# RobotCtrl_V2_Mother-board.net
KiCad netlist of a schematic drawn in Altium Designer
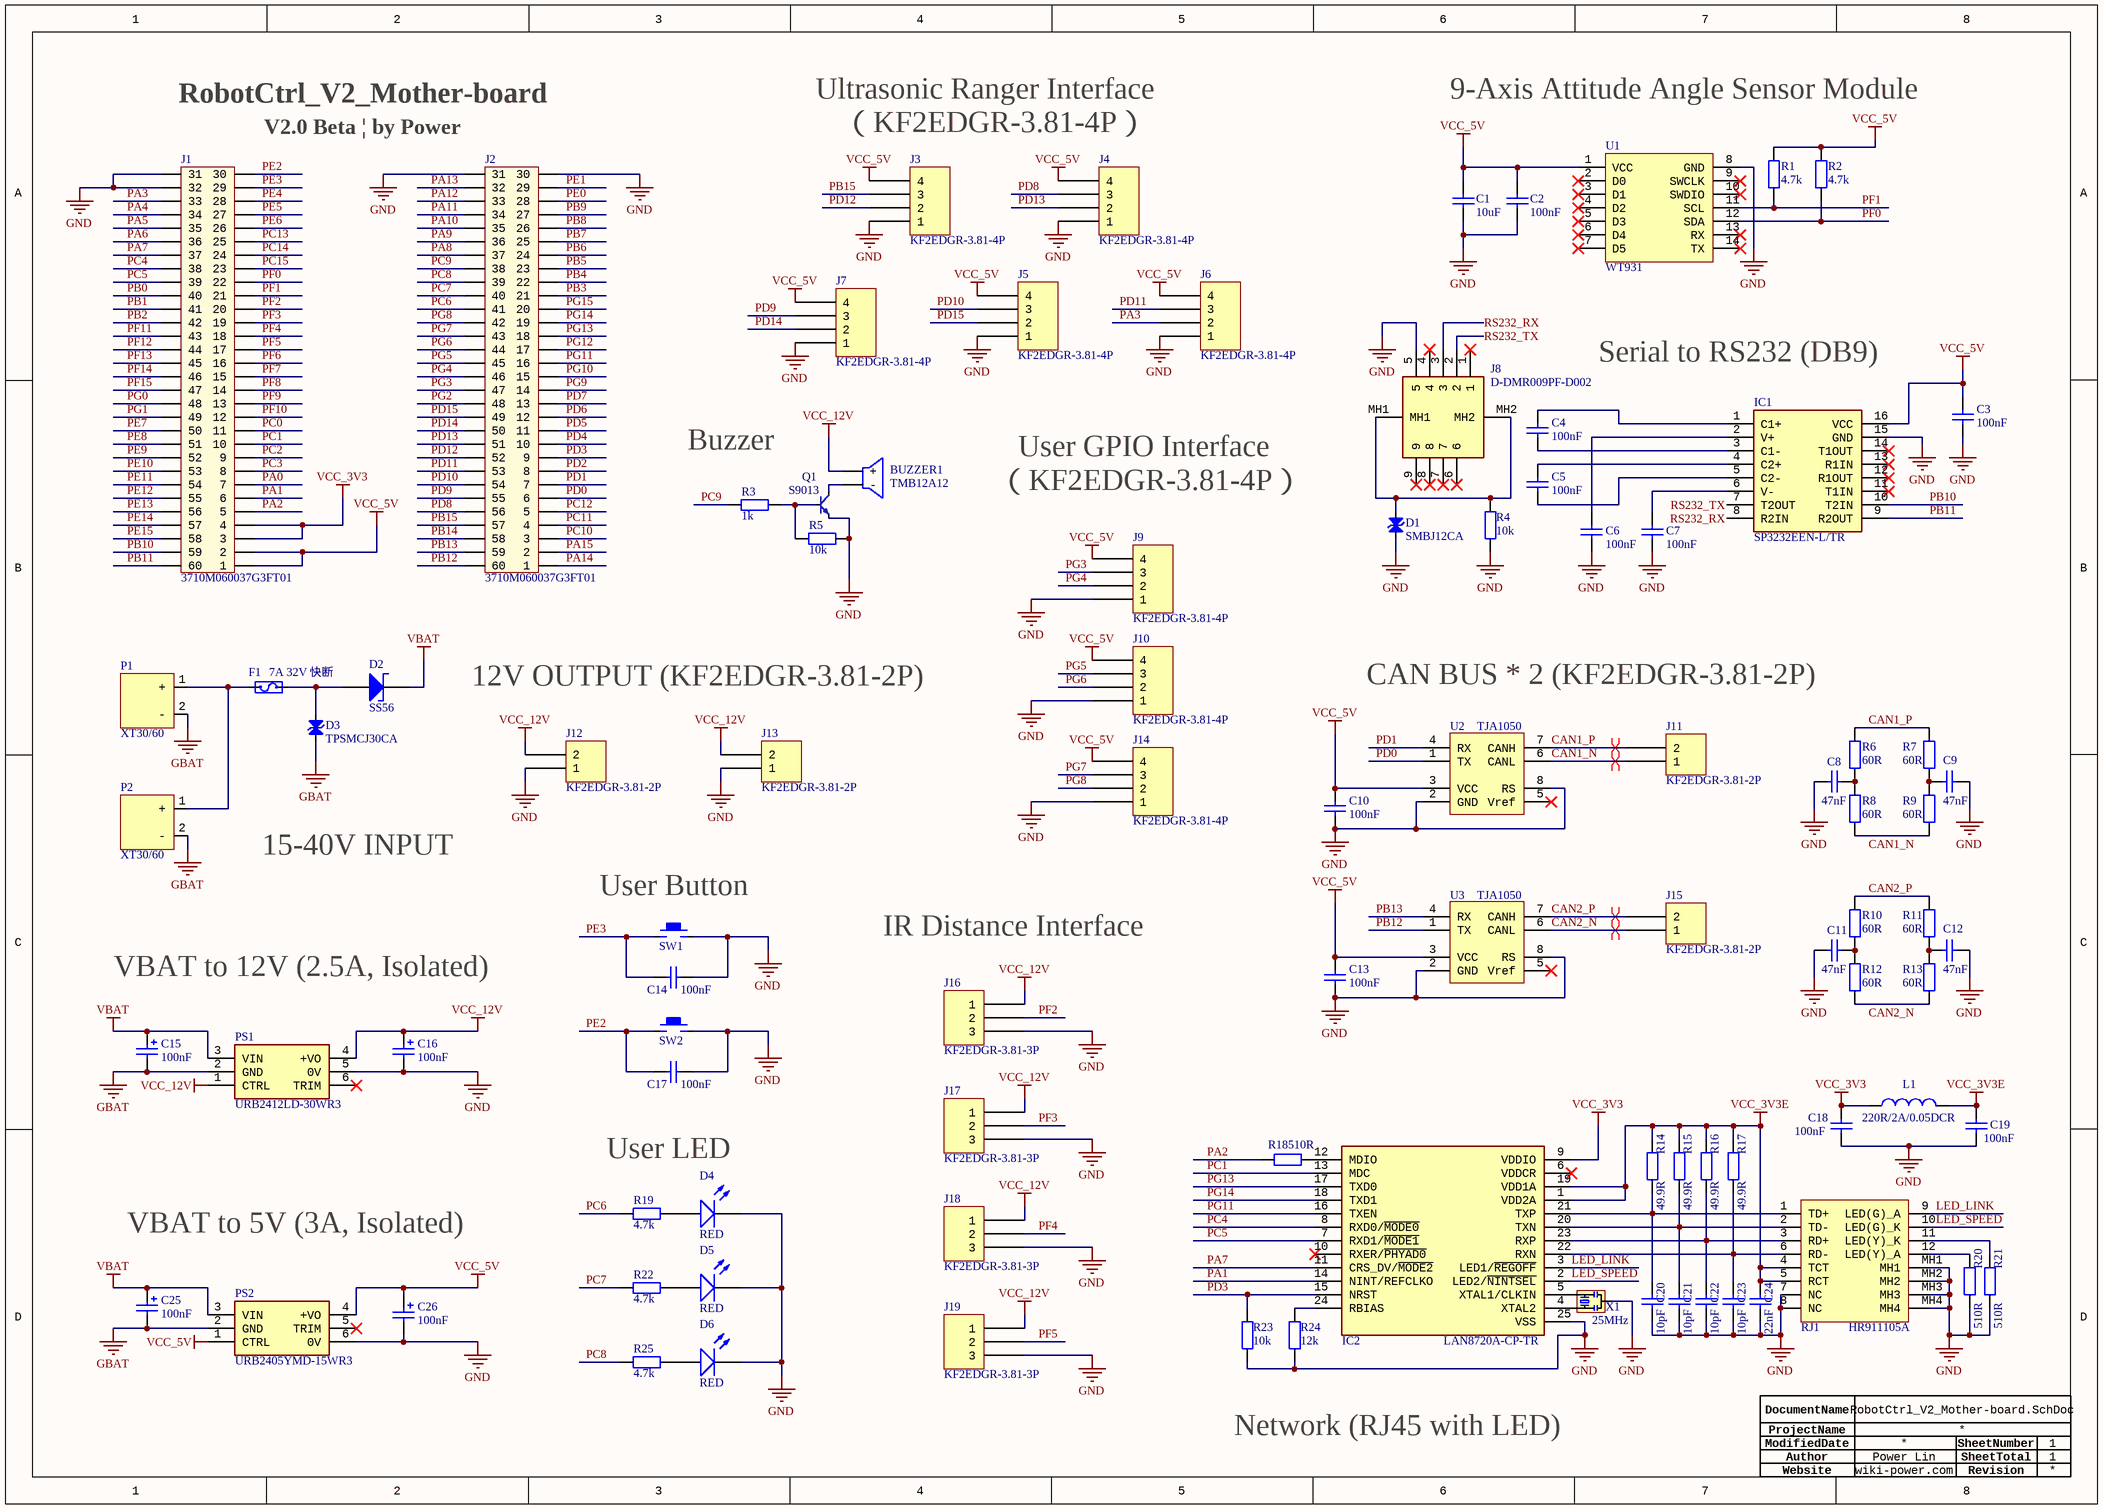
[diagram p0: RobotCtrl_V2_Mother-board.SchDoc]

(export (version "E")
  (design (tool "Eeschema 10.0.6"))
  (components
    (comp (ref "BUZZER1")
      (value "TMB12A12")
      (footprint "DIP,P=7.6mm")
      (description "TMB12A12 有源蜂鸣器")
      (libsource (lib "Power_Lib_Altium") (part "BUZZER"))
    )
    (comp (ref "C1")
      (value "10uF")
      (footprint "CAP-0603")
      (description "贴片电容")
      (libsource (lib "Power_Lib_Altium") (part "CAP"))
    )
    (comp (ref "C2")
      (value "100nF")
      (footprint "CAP-0603")
      (description "贴片电容")
      (libsource (lib "Power_Lib_Altium") (part "CAP"))
    )
    (comp (ref "C3")
      (value "100nF")
      (footprint "CAP-0603")
      (description "贴片电容")
      (libsource (lib "Power_Lib_Altium") (part "CAP"))
    )
    (comp (ref "C4")
      (value "100nF")
      (footprint "CAP-0603")
      (description "贴片电容")
      (libsource (lib "Power_Lib_Altium") (part "CAP"))
    )
    (comp (ref "C5")
      (value "100nF")
      (footprint "CAP-0603")
      (description "贴片电容")
      (libsource (lib "Power_Lib_Altium") (part "CAP"))
    )
    (comp (ref "C6")
      (value "100nF")
      (footprint "CAP-0603")
      (description "贴片电容")
      (libsource (lib "Power_Lib_Altium") (part "CAP"))
    )
    (comp (ref "C7")
      (value "100nF")
      (footprint "CAP-0603")
      (description "贴片电容")
      (libsource (lib "Power_Lib_Altium") (part "CAP"))
    )
    (comp (ref "C8")
      (value "47nF")
      (footprint "CAP-0603")
      (description "贴片电容")
      (libsource (lib "Power_Lib_Altium") (part "CAP"))
    )
    (comp (ref "C9")
      (value "47nF")
      (footprint "CAP-0603")
      (description "贴片电容")
      (libsource (lib "Power_Lib_Altium") (part "CAP"))
    )
    (comp (ref "C10")
      (value "100nF")
      (footprint "CAP-0603")
      (description "贴片电容")
      (libsource (lib "Power_Lib_Altium") (part "CAP"))
    )
    (comp (ref "C11")
      (value "47nF")
      (footprint "CAP-0603")
      (description "贴片电容")
      (libsource (lib "Power_Lib_Altium") (part "CAP"))
    )
    (comp (ref "C12")
      (value "47nF")
      (footprint "CAP-0603")
      (description "贴片电容")
      (libsource (lib "Power_Lib_Altium") (part "CAP"))
    )
    (comp (ref "C13")
      (value "100nF")
      (footprint "CAP-0603")
      (description "贴片电容")
      (libsource (lib "Power_Lib_Altium") (part "CAP"))
    )
    (comp (ref "C14")
      (value "100nF")
      (footprint "CAP-0603")
      (description "贴片电容")
      (libsource (lib "Power_Lib_Altium") (part "CAP"))
    )
    (comp (ref "C15")
      (value "100nF")
      (footprint "CAP-AUX-3216")
      (description "KM101M050F115A")
      (libsource (lib "Power_Lib_Altium") (part "CAP-POL"))
    )
    (comp (ref "C16")
      (value "100nF")
      (footprint "CAP-AUX-3216")
      (description "KM101M050F115A")
      (libsource (lib "Power_Lib_Altium") (part "CAP-POL"))
    )
    (comp (ref "C17")
      (value "100nF")
      (footprint "CAP-0603")
      (description "贴片电容")
      (libsource (lib "Power_Lib_Altium") (part "CAP"))
    )
    (comp (ref "C18")
      (value "100nF")
      (footprint "CAP-0603")
      (description "贴片电容")
      (libsource (lib "Power_Lib_Altium") (part "CAP"))
    )
    (comp (ref "C19")
      (value "100nF")
      (footprint "CAP-0603")
      (description "贴片电容")
      (libsource (lib "Power_Lib_Altium") (part "CAP"))
    )
    (comp (ref "C20")
      (value "10pF")
      (footprint "CAP-0603")
      (description "贴片电容")
      (libsource (lib "Power_Lib_Altium") (part "CAP"))
    )
    (comp (ref "C21")
      (value "10pF")
      (footprint "CAP-0603")
      (description "贴片电容")
      (libsource (lib "Power_Lib_Altium") (part "CAP"))
    )
    (comp (ref "C22")
      (value "10pF")
      (footprint "CAP-0603")
      (description "贴片电容")
      (libsource (lib "Power_Lib_Altium") (part "CAP"))
    )
    (comp (ref "C23")
      (value "10pF")
      (footprint "CAP-0603")
      (description "贴片电容")
      (libsource (lib "Power_Lib_Altium") (part "CAP"))
    )
    (comp (ref "C24")
      (value "22nF")
      (footprint "CAP-0603")
      (description "贴片电容")
      (libsource (lib "Power_Lib_Altium") (part "CAP"))
    )
    (comp (ref "C25")
      (value "100nF")
      (footprint "CAP-AUX-3216")
      (description "KM101M050F115A")
      (libsource (lib "Power_Lib_Altium") (part "CAP-POL"))
    )
    (comp (ref "C26")
      (value "100nF")
      (footprint "CAP-AUX-3216")
      (description "KM101M050F115A")
      (libsource (lib "Power_Lib_Altium") (part "CAP-POL"))
    )
    (comp (ref "D1")
      (value "SMBJ12CA")
      (footprint "DO-214AA/SMB")
      (libsource (lib "Power_Lib_Altium") (part "TVS_C"))
    )
    (comp (ref "D2")
      (value "SS56")
      (footprint "DO-214AB/SMC")
      (description "肖特基二极管")
      (libsource (lib "Power_Lib_Altium") (part "DIODE_Schottky"))
    )
    (comp (ref "D3")
      (value "TPSMCJ30CA")
      (footprint "DO-214AB/SMC")
      (libsource (lib "Power_Lib_Altium") (part "TVS_C"))
    )
    (comp (ref "D4")
      (value "RED")
      (footprint "LED-0603")
      (description "发光二极管")
      (libsource (lib "Power_Lib_Altium") (part "LED"))
    )
    (comp (ref "D5")
      (value "RED")
      (footprint "LED-0603")
      (description "发光二极管")
      (libsource (lib "Power_Lib_Altium") (part "LED"))
    )
    (comp (ref "D6")
      (value "RED")
      (footprint "LED-0603")
      (description "发光二极管")
      (libsource (lib "Power_Lib_Altium") (part "LED"))
    )
    (comp (ref "F1")
      (value "7A 32V 快断")
      (footprint "FUSE_1206")
      (description "0437007.WR")
      (libsource (lib "Power_Lib_Altium") (part "Fuse"))
    )
    (comp (ref "IC1")
      (value "SP3232EEN-L/TR")
      (footprint "SOIC-16_150mil")
      (description "RS232 芯片")
      (fields (field (name "MOUSER PART NUMBER") "701-SP3232EEN-L/TR"))
      (libsource (lib "Power_Lib_Altium") (part "SP3232EEN"))
    )
    (comp (ref "IC2")
      (value "LAN8720A-CP-TR")
      (footprint "QFN-24-4x4")
      (description "Integrated Circuit")
      (fields (field (name "MOUSER PART NUMBER") "886-LAN8720A-CP-TR"))
      (libsource (lib "Power_Lib_Altium") (part "LAN8720A-CP-TR"))
    )
    (comp (ref "J1")
      (value "3710M060037G3FT01")
      (footprint "3710M060037G3FT01")
      (description "B2B Connector")
      (libsource (lib "Power_Lib_Altium") (part "3710M/F"))
    )
    (comp (ref "J2")
      (value "3710M060037G3FT01")
      (footprint "3710M060037G3FT01")
      (description "B2B Connector")
      (libsource (lib "Power_Lib_Altium") (part "3710M/F"))
    )
    (comp (ref "J3")
      (value "KF2EDGR-3.81-4P")
      (footprint "FCI 06-381-4PIN")
      (description "TERM BLOCK HDR 4POS 90DEG 3.81MM")
      (fields (field (name "PART NUMBER") "OQ0432510000G") (field (name "MANUFACTURER") "Amphenol Anytek"))
      (libsource (lib "Power_Lib_Altium") (part "KF2EDGR-3.81-4P"))
    )
    (comp (ref "J4")
      (value "KF2EDGR-3.81-4P")
      (footprint "FCI 06-381-4PIN")
      (description "TERM BLOCK HDR 4POS 90DEG 3.81MM")
      (fields (field (name "PART NUMBER") "OQ0432510000G") (field (name "MANUFACTURER") "Amphenol Anytek"))
      (libsource (lib "Power_Lib_Altium") (part "KF2EDGR-3.81-4P"))
    )
    (comp (ref "J5")
      (value "KF2EDGR-3.81-4P")
      (footprint "FCI 06-381-4PIN")
      (description "TERM BLOCK HDR 4POS 90DEG 3.81MM")
      (fields (field (name "PART NUMBER") "OQ0432510000G") (field (name "MANUFACTURER") "Amphenol Anytek"))
      (libsource (lib "Power_Lib_Altium") (part "KF2EDGR-3.81-4P"))
    )
    (comp (ref "J6")
      (value "KF2EDGR-3.81-4P")
      (footprint "FCI 06-381-4PIN")
      (description "TERM BLOCK HDR 4POS 90DEG 3.81MM")
      (fields (field (name "PART NUMBER") "OQ0432510000G") (field (name "MANUFACTURER") "Amphenol Anytek"))
      (libsource (lib "Power_Lib_Altium") (part "KF2EDGR-3.81-4P"))
    )
    (comp (ref "J7")
      (value "KF2EDGR-3.81-4P")
      (footprint "FCI 06-381-4PIN")
      (description "TERM BLOCK HDR 4POS 90DEG 3.81MM")
      (fields (field (name "PART NUMBER") "OQ0432510000G") (field (name "MANUFACTURER") "Amphenol Anytek"))
      (libsource (lib "Power_Lib_Altium") (part "KF2EDGR-3.81-4P"))
    )
    (comp (ref "J8")
      (value "D-DMR009PF-D002")
      (footprint "Through Hole,P=2.77mm")
      (description "D-Sub 连接器")
      (fields
        (field (name "MANUFACTURER_PART_NUMBER") "5747844-5")
        (field (name "MOUSER PART NUMBER") "571-5747844-5")
      )
      (libsource (lib "Power_Lib_Altium") (part "DB9"))
    )
    (comp (ref "J9")
      (value "KF2EDGR-3.81-4P")
      (footprint "FCI 06-381-4PIN")
      (description "TERM BLOCK HDR 4POS 90DEG 3.81MM")
      (fields (field (name "PART NUMBER") "OQ0432510000G") (field (name "MANUFACTURER") "Amphenol Anytek"))
      (libsource (lib "Power_Lib_Altium") (part "KF2EDGR-3.81-4P"))
    )
    (comp (ref "J10")
      (value "KF2EDGR-3.81-4P")
      (footprint "FCI 06-381-4PIN")
      (description "TERM BLOCK HDR 4POS 90DEG 3.81MM")
      (fields (field (name "PART NUMBER") "OQ0432510000G") (field (name "MANUFACTURER") "Amphenol Anytek"))
      (libsource (lib "Power_Lib_Altium") (part "KF2EDGR-3.81-4P"))
    )
    (comp (ref "J11")
      (value "KF2EDGR-3.81-2P")
      (footprint "FCI 06-381-2PIN")
      (description "TERM BLOCK HDR 2POS 90DEG 3.81MM")
      (fields (field (name "PART NUMBER") "OQ0232510000G") (field (name "MANUFACTURER") "Amphenol Anytek"))
      (libsource (lib "Power_Lib_Altium") (part "KF2EDGR-3.81-2P"))
    )
    (comp (ref "J12")
      (value "KF2EDGR-3.81-2P")
      (footprint "FCI 06-381-2PIN")
      (description "TERM BLOCK HDR 2POS 90DEG 3.81MM")
      (fields (field (name "PART NUMBER") "OQ0232510000G") (field (name "MANUFACTURER") "Amphenol Anytek"))
      (libsource (lib "Power_Lib_Altium") (part "KF2EDGR-3.81-2P"))
    )
    (comp (ref "J13")
      (value "KF2EDGR-3.81-2P")
      (footprint "FCI 06-381-2PIN")
      (description "TERM BLOCK HDR 2POS 90DEG 3.81MM")
      (fields (field (name "PART NUMBER") "OQ0232510000G") (field (name "MANUFACTURER") "Amphenol Anytek"))
      (libsource (lib "Power_Lib_Altium") (part "KF2EDGR-3.81-2P"))
    )
    (comp (ref "J14")
      (value "KF2EDGR-3.81-4P")
      (footprint "FCI 06-381-4PIN")
      (description "TERM BLOCK HDR 4POS 90DEG 3.81MM")
      (fields (field (name "PART NUMBER") "OQ0432510000G") (field (name "MANUFACTURER") "Amphenol Anytek"))
      (libsource (lib "Power_Lib_Altium") (part "KF2EDGR-3.81-4P"))
    )
    (comp (ref "J15")
      (value "KF2EDGR-3.81-2P")
      (footprint "FCI 06-381-2PIN")
      (description "TERM BLOCK HDR 2POS 90DEG 3.81MM")
      (fields (field (name "PART NUMBER") "OQ0232510000G") (field (name "MANUFACTURER") "Amphenol Anytek"))
      (libsource (lib "Power_Lib_Altium") (part "KF2EDGR-3.81-2P"))
    )
    (comp (ref "J16")
      (value "KF2EDGR-3.81-3P")
      (footprint "FCI 06-381-3PIN")
      (description "TERM BLOCK HDR 3POS 90DEG 3.81MM")
      (fields (field (name "MANUFACTURER") "Amphenol Anytek") (field (name "PART NUMBER") "OQ0332510000G"))
      (libsource (lib "Power_Lib_Altium") (part "KF2EDGR-3.81-3P"))
    )
    (comp (ref "J17")
      (value "KF2EDGR-3.81-3P")
      (footprint "FCI 06-381-3PIN")
      (description "TERM BLOCK HDR 3POS 90DEG 3.81MM")
      (fields (field (name "MANUFACTURER") "Amphenol Anytek") (field (name "PART NUMBER") "OQ0332510000G"))
      (libsource (lib "Power_Lib_Altium") (part "KF2EDGR-3.81-3P"))
    )
    (comp (ref "J18")
      (value "KF2EDGR-3.81-3P")
      (footprint "FCI 06-381-3PIN")
      (description "TERM BLOCK HDR 3POS 90DEG 3.81MM")
      (fields (field (name "MANUFACTURER") "Amphenol Anytek") (field (name "PART NUMBER") "OQ0332510000G"))
      (libsource (lib "Power_Lib_Altium") (part "KF2EDGR-3.81-3P"))
    )
    (comp (ref "J19")
      (value "KF2EDGR-3.81-3P")
      (footprint "FCI 06-381-3PIN")
      (description "TERM BLOCK HDR 3POS 90DEG 3.81MM")
      (fields (field (name "MANUFACTURER") "Amphenol Anytek") (field (name "PART NUMBER") "OQ0332510000G"))
      (libsource (lib "Power_Lib_Altium") (part "KF2EDGR-3.81-3P"))
    )
    (comp (ref "L1")
      (value "220R/2A/0.05DCR")
      (footprint "L-0603")
      (description "BLM18KG221SN1D")
      (libsource (lib "Power_Lib_Altium") (part "BEAD"))
    )
    (comp (ref "P1")
      (value "XT30/60")
      (footprint "XT60PW-M")
      (libsource (lib "Power_Lib_Altium") (part "XT30/60"))
    )
    (comp (ref "P2")
      (value "XT30/60")
      (footprint "XT60PW-M")
      (libsource (lib "Power_Lib_Altium") (part "XT30/60"))
    )
    (comp (ref "PS1")
      (value "URB2412LD-30WR3")
      (footprint "URB2412LD30WR3")
      (description "金升阳隔离电源")
      (fields (field (name "MANUFACTURER_PART_NUMBER") "URB2412LD-30WHR3"))
      (libsource (lib "Power_Lib_Altium") (part "URB2412LD-30WR3"))
    )
    (comp (ref "PS2")
      (value "URB2405YMD-15WR3")
      (footprint "URB2405YMD15WR3")
      (description "金升阳隔离电源")
      (fields (field (name "MANUFACTURER_PART_NUMBER") "URB2405YMD-10WR3"))
      (libsource (lib "Power_Lib_Altium") (part "URB2405YMD-15WR3"))
    )
    (comp (ref "Q1")
      (value "S9013")
      (footprint "SOT-23-3")
      (libsource (lib "Power_Lib_Altium") (part "BJT_NPN"))
    )
    (comp (ref "R1")
      (value "4.7k")
      (footprint "R-0603")
      (description "贴片电阻")
      (libsource (lib "") (part "RES_1"))
    )
    (comp (ref "R2")
      (value "4.7k")
      (footprint "R-0603")
      (description "贴片电阻")
      (libsource (lib "") (part "RES_1"))
    )
    (comp (ref "R3")
      (value "1k")
      (footprint "R-0603")
      (description "贴片电阻")
      (libsource (lib "") (part "RES_3"))
    )
    (comp (ref "R4")
      (value "10k")
      (footprint "R-0603")
      (description "贴片电阻")
      (libsource (lib "") (part "RES_1"))
    )
    (comp (ref "R5")
      (value "10k")
      (footprint "R-0603")
      (description "贴片电阻")
      (libsource (lib "Power_Lib_Altium") (part "RES"))
    )
    (comp (ref "R6")
      (value "60R")
      (footprint "R-0603")
      (description "贴片电阻")
      (libsource (lib "") (part "RES_2"))
    )
    (comp (ref "R7")
      (value "60R")
      (footprint "R-0603")
      (description "贴片电阻")
      (libsource (lib "") (part "RES_1"))
    )
    (comp (ref "R8")
      (value "60R")
      (footprint "R-0603")
      (description "贴片电阻")
      (libsource (lib "") (part "RES_2"))
    )
    (comp (ref "R9")
      (value "60R")
      (footprint "R-0603")
      (description "贴片电阻")
      (libsource (lib "") (part "RES_1"))
    )
    (comp (ref "R10")
      (value "60R")
      (footprint "R-0603")
      (description "贴片电阻")
      (libsource (lib "") (part "RES_2"))
    )
    (comp (ref "R11")
      (value "60R")
      (footprint "R-0603")
      (description "贴片电阻")
      (libsource (lib "") (part "RES_1"))
    )
    (comp (ref "R12")
      (value "60R")
      (footprint "R-0603")
      (description "贴片电阻")
      (libsource (lib "") (part "RES_2"))
    )
    (comp (ref "R13")
      (value "60R")
      (footprint "R-0603")
      (description "贴片电阻")
      (libsource (lib "") (part "RES_1"))
    )
    (comp (ref "R14")
      (value "49.9R")
      (footprint "R-0603")
      (description "贴片电阻")
      (libsource (lib "") (part "RES_1"))
    )
    (comp (ref "R15")
      (value "49.9R")
      (footprint "R-0603")
      (description "贴片电阻")
      (libsource (lib "") (part "RES_1"))
    )
    (comp (ref "R16")
      (value "49.9R")
      (footprint "R-0603")
      (description "贴片电阻")
      (libsource (lib "") (part "RES_1"))
    )
    (comp (ref "R17")
      (value "49.9R")
      (footprint "R-0603")
      (description "贴片电阻")
      (libsource (lib "") (part "RES_1"))
    )
    (comp (ref "R18")
      (value "510R")
      (footprint "R-0603")
      (description "贴片电阻")
      (libsource (lib "Power_Lib_Altium") (part "RES"))
    )
    (comp (ref "R19")
      (value "4.7k")
      (footprint "R-0603")
      (description "贴片电阻")
      (libsource (lib "Power_Lib_Altium") (part "RES"))
    )
    (comp (ref "R20")
      (value "510R")
      (footprint "R-0603")
      (description "贴片电阻")
      (libsource (lib "") (part "RES_1"))
    )
    (comp (ref "R21")
      (value "510R")
      (footprint "R-0603")
      (description "贴片电阻")
      (libsource (lib "") (part "RES_1"))
    )
    (comp (ref "R22")
      (value "4.7k")
      (footprint "R-0603")
      (description "贴片电阻")
      (libsource (lib "Power_Lib_Altium") (part "RES"))
    )
    (comp (ref "R23")
      (value "10k")
      (footprint "R-0603")
      (description "贴片电阻")
      (libsource (lib "") (part "RES_2"))
    )
    (comp (ref "R24")
      (value "12k")
      (footprint "R-0603")
      (description "贴片电阻")
      (libsource (lib "") (part "RES_2"))
    )
    (comp (ref "R25")
      (value "4.7k")
      (footprint "R-0603")
      (description "贴片电阻")
      (libsource (lib "Power_Lib_Altium") (part "RES"))
    )
    (comp (ref "RJ1")
      (value "HR911105A")
      (footprint "HR911105A")
      (libsource (lib "Power_Lib_Altium") (part "RJ45_LED"))
    )
    (comp (ref "SW1")
      (value "KEY")
      (footprint "KEY-4P-4.2*3.4*2.5")
      (description "按键开关")
      (libsource (lib "Power_Lib_Altium") (part "KEY"))
    )
    (comp (ref "SW2")
      (value "KEY")
      (footprint "KEY-4P-4.2*3.4*2.5")
      (description "按键开关")
      (libsource (lib "Power_Lib_Altium") (part "KEY"))
    )
    (comp (ref "U1")
      (value "WT931")
      (footprint "WT931")
      (description "陀螺仪模组")
      (libsource (lib "Power_Lib_Altium") (part "WT931"))
    )
    (comp (ref "U2")
      (value "TJA1050")
      (footprint "SOIC_8")
      (description "CAN 控制器（5V）")
      (libsource (lib "Power_Lib_Altium") (part "TJA1050"))
    )
    (comp (ref "U3")
      (value "TJA1050")
      (footprint "SOIC_8")
      (description "CAN 控制器（5V）")
      (libsource (lib "Power_Lib_Altium") (part "TJA1050"))
    )
    (comp (ref "X1")
      (value "25MHz")
      (footprint "SMD3213-3P")
      (description "CSTCE25M00G51-R0")
      (libsource (lib "Power_Lib_Altium") (part "XTAL"))
    )
  )
  (nets
    (net (code "1") (name "/CAN1_N") (class "Default")
      (node (ref "J11") (pin "1") (pinfunction "1_1") (pintype "passive"))
      (node (ref "R8") (pin "2") (pinfunction "2_2") (pintype "passive"))
      (node (ref "R9") (pin "1") (pinfunction "1_1") (pintype "passive"))
      (node (ref "U2") (pin "6") (pinfunction "CANL_6") (pintype "passive"))
    )
    (net (code "2") (name "/CAN1_P") (class "Default")
      (node (ref "J11") (pin "2") (pinfunction "2_2") (pintype "passive"))
      (node (ref "R6") (pin "1") (pinfunction "1_1") (pintype "passive"))
      (node (ref "R7") (pin "2") (pinfunction "2_2") (pintype "passive"))
      (node (ref "U2") (pin "7") (pinfunction "CANH_7") (pintype "passive"))
    )
    (net (code "3") (name "/CAN2_N") (class "Default")
      (node (ref "J15") (pin "1") (pinfunction "1_1") (pintype "passive"))
      (node (ref "R12") (pin "2") (pinfunction "2_2") (pintype "passive"))
      (node (ref "R13") (pin "1") (pinfunction "1_1") (pintype "passive"))
      (node (ref "U3") (pin "6") (pinfunction "CANL_6") (pintype "passive"))
    )
    (net (code "4") (name "/CAN2_P") (class "Default")
      (node (ref "J15") (pin "2") (pinfunction "2_2") (pintype "passive"))
      (node (ref "R10") (pin "1") (pinfunction "1_1") (pintype "passive"))
      (node (ref "R11") (pin "2") (pinfunction "2_2") (pintype "passive"))
      (node (ref "U3") (pin "7") (pinfunction "CANH_7") (pintype "passive"))
    )
    (net (code "5") (name "/LED_LINK") (class "Default")
      (node (ref "IC2") (pin "3") (pinfunction "LED1/~{REGOFF}_3") (pintype "passive"))
      (node (ref "RJ1") (pin "9") (pinfunction "LED(G)_A_9") (pintype "passive"))
    )
    (net (code "6") (name "/LED_SPEED") (class "Default")
      (node (ref "IC2") (pin "2") (pinfunction "LED2/~{NINTSEL}_2") (pintype "passive"))
      (node (ref "RJ1") (pin "10") (pinfunction "LED(G)_K_10") (pintype "passive"))
    )
    (net (code "7") (name "/PA0") (class "Default")
      (node (ref "J1") (pin "7") (pinfunction "7_7") (pintype "passive"))
    )
    (net (code "8") (name "/PA1") (class "Default")
      (node (ref "IC2") (pin "14") (pinfunction "NINT/REFCLKO_14") (pintype "passive"))
      (node (ref "J1") (pin "6") (pinfunction "6_6") (pintype "passive"))
    )
    (net (code "9") (name "/PA2") (class "Default")
      (node (ref "J1") (pin "5") (pinfunction "5_5") (pintype "passive"))
      (node (ref "R18") (pin "2") (pinfunction "2_2") (pintype "passive"))
    )
    (net (code "10") (name "/PA3") (class "Default")
      (node (ref "J1") (pin "33") (pinfunction "33_33") (pintype "passive"))
      (node (ref "J6") (pin "2") (pinfunction "2_2") (pintype "passive"))
    )
    (net (code "11") (name "/PA4") (class "Default")
      (node (ref "J1") (pin "34") (pinfunction "34_34") (pintype "passive"))
    )
    (net (code "12") (name "/PA5") (class "Default")
      (node (ref "J1") (pin "35") (pinfunction "35_35") (pintype "passive"))
    )
    (net (code "13") (name "/PA6") (class "Default")
      (node (ref "J1") (pin "36") (pinfunction "36_36") (pintype "passive"))
    )
    (net (code "14") (name "/PA7") (class "Default")
      (node (ref "IC2") (pin "11") (pinfunction "CRS_DV/~{MODE2}_11") (pintype "passive"))
      (node (ref "J1") (pin "37") (pinfunction "37_37") (pintype "passive"))
    )
    (net (code "15") (name "/PA8") (class "Default")
      (node (ref "J2") (pin "37") (pinfunction "37_37") (pintype "passive"))
    )
    (net (code "16") (name "/PA9") (class "Default")
      (node (ref "J2") (pin "36") (pinfunction "36_36") (pintype "passive"))
    )
    (net (code "17") (name "/PA10") (class "Default")
      (node (ref "J2") (pin "35") (pinfunction "35_35") (pintype "passive"))
    )
    (net (code "18") (name "/PA11") (class "Default")
      (node (ref "J2") (pin "34") (pinfunction "34_34") (pintype "passive"))
    )
    (net (code "19") (name "/PA12") (class "Default")
      (node (ref "J2") (pin "33") (pinfunction "33_33") (pintype "passive"))
    )
    (net (code "20") (name "/PA13") (class "Default")
      (node (ref "J2") (pin "32") (pinfunction "32_32") (pintype "passive"))
    )
    (net (code "21") (name "/PA14") (class "Default")
      (node (ref "J2") (pin "1") (pinfunction "1_1") (pintype "passive"))
    )
    (net (code "22") (name "/PA15") (class "Default")
      (node (ref "J2") (pin "2") (pinfunction "2_2") (pintype "passive"))
    )
    (net (code "23") (name "/PB0") (class "Default")
      (node (ref "J1") (pin "40") (pinfunction "40_40") (pintype "passive"))
    )
    (net (code "24") (name "/PB1") (class "Default")
      (node (ref "J1") (pin "41") (pinfunction "41_41") (pintype "passive"))
    )
    (net (code "25") (name "/PB2") (class "Default")
      (node (ref "J1") (pin "42") (pinfunction "42_42") (pintype "passive"))
    )
    (net (code "26") (name "/PB3") (class "Default")
      (node (ref "J2") (pin "21") (pinfunction "21_21") (pintype "passive"))
    )
    (net (code "27") (name "/PB4") (class "Default")
      (node (ref "J2") (pin "22") (pinfunction "22_22") (pintype "passive"))
    )
    (net (code "28") (name "/PB5") (class "Default")
      (node (ref "J2") (pin "23") (pinfunction "23_23") (pintype "passive"))
    )
    (net (code "29") (name "/PB6") (class "Default")
      (node (ref "J2") (pin "24") (pinfunction "24_24") (pintype "passive"))
    )
    (net (code "30") (name "/PB7") (class "Default")
      (node (ref "J2") (pin "25") (pinfunction "25_25") (pintype "passive"))
    )
    (net (code "31") (name "/PB8") (class "Default")
      (node (ref "J2") (pin "26") (pinfunction "26_26") (pintype "passive"))
    )
    (net (code "32") (name "/PB9") (class "Default")
      (node (ref "J2") (pin "27") (pinfunction "27_27") (pintype "passive"))
    )
    (net (code "33") (name "/PB10") (class "Default")
      (node (ref "IC1") (pin "10") (pinfunction "T2IN_10") (pintype "passive"))
      (node (ref "J1") (pin "59") (pinfunction "59_59") (pintype "passive"))
    )
    (net (code "34") (name "/PB11") (class "Default")
      (node (ref "IC1") (pin "9") (pinfunction "R2OUT_9") (pintype "passive"))
      (node (ref "J1") (pin "60") (pinfunction "60_60") (pintype "passive"))
    )
    (net (code "35") (name "/PB12") (class "Default")
      (node (ref "J2") (pin "60") (pinfunction "60_60") (pintype "passive"))
      (node (ref "U3") (pin "1") (pinfunction "TX_1") (pintype "passive"))
    )
    (net (code "36") (name "/PB13") (class "Default")
      (node (ref "J2") (pin "59") (pinfunction "59_59") (pintype "passive"))
      (node (ref "U3") (pin "4") (pinfunction "RX_4") (pintype "passive"))
    )
    (net (code "37") (name "/PB14") (class "Default")
      (node (ref "J2") (pin "58") (pinfunction "58_58") (pintype "passive"))
    )
    (net (code "38") (name "/PB15") (class "Default")
      (node (ref "J2") (pin "57") (pinfunction "57_57") (pintype "passive"))
      (node (ref "J3") (pin "3") (pinfunction "3_3") (pintype "passive"))
    )
    (net (code "39") (name "/PC0") (class "Default")
      (node (ref "J1") (pin "11") (pinfunction "11_11") (pintype "passive"))
    )
    (net (code "40") (name "/PC1") (class "Default")
      (node (ref "IC2") (pin "13") (pinfunction "MDC_13") (pintype "passive"))
      (node (ref "J1") (pin "10") (pinfunction "10_10") (pintype "passive"))
    )
    (net (code "41") (name "/PC2") (class "Default")
      (node (ref "J1") (pin "9") (pinfunction "9_9") (pintype "passive"))
    )
    (net (code "42") (name "/PC3") (class "Default")
      (node (ref "J1") (pin "8") (pinfunction "8_8") (pintype "passive"))
    )
    (net (code "43") (name "/PC4") (class "Default")
      (node (ref "IC2") (pin "8") (pinfunction "RXD0/~{MODE0}_8") (pintype "passive"))
      (node (ref "J1") (pin "38") (pinfunction "38_38") (pintype "passive"))
    )
    (net (code "44") (name "/PC5") (class "Default")
      (node (ref "IC2") (pin "7") (pinfunction "RXD1/~{MODE1}_7") (pintype "passive"))
      (node (ref "J1") (pin "39") (pinfunction "39_39") (pintype "passive"))
    )
    (net (code "45") (name "/PC6") (class "Default")
      (node (ref "J2") (pin "41") (pinfunction "41_41") (pintype "passive"))
      (node (ref "R19") (pin "2") (pinfunction "2_2") (pintype "passive"))
    )
    (net (code "46") (name "/PC7") (class "Default")
      (node (ref "J2") (pin "40") (pinfunction "40_40") (pintype "passive"))
      (node (ref "R22") (pin "2") (pinfunction "2_2") (pintype "passive"))
    )
    (net (code "47") (name "/PC8") (class "Default")
      (node (ref "J2") (pin "39") (pinfunction "39_39") (pintype "passive"))
      (node (ref "R25") (pin "2") (pinfunction "2_2") (pintype "passive"))
    )
    (net (code "48") (name "/PC9") (class "Default")
      (node (ref "J2") (pin "38") (pinfunction "38_38") (pintype "passive"))
      (node (ref "R3") (pin "1") (pinfunction "1_1") (pintype "passive"))
    )
    (net (code "49") (name "/PC10") (class "Default")
      (node (ref "J2") (pin "3") (pinfunction "3_3") (pintype "passive"))
    )
    (net (code "50") (name "/PC11") (class "Default")
      (node (ref "J2") (pin "4") (pinfunction "4_4") (pintype "passive"))
    )
    (net (code "51") (name "/PC12") (class "Default")
      (node (ref "J2") (pin "5") (pinfunction "5_5") (pintype "passive"))
    )
    (net (code "52") (name "/PC13") (class "Default")
      (node (ref "J1") (pin "25") (pinfunction "25_25") (pintype "passive"))
    )
    (net (code "53") (name "/PC14") (class "Default")
      (node (ref "J1") (pin "24") (pinfunction "24_24") (pintype "passive"))
    )
    (net (code "54") (name "/PC15") (class "Default")
      (node (ref "J1") (pin "23") (pinfunction "23_23") (pintype "passive"))
    )
    (net (code "55") (name "/PD0") (class "Default")
      (node (ref "J2") (pin "6") (pinfunction "6_6") (pintype "passive"))
      (node (ref "U2") (pin "1") (pinfunction "TX_1") (pintype "passive"))
    )
    (net (code "56") (name "/PD1") (class "Default")
      (node (ref "J2") (pin "7") (pinfunction "7_7") (pintype "passive"))
      (node (ref "U2") (pin "4") (pinfunction "RX_4") (pintype "passive"))
    )
    (net (code "57") (name "/PD2") (class "Default")
      (node (ref "J2") (pin "8") (pinfunction "8_8") (pintype "passive"))
    )
    (net (code "58") (name "/PD3") (class "Default")
      (node (ref "IC2") (pin "15") (pinfunction "NRST_15") (pintype "passive"))
      (node (ref "J2") (pin "9") (pinfunction "9_9") (pintype "passive"))
      (node (ref "R23") (pin "1") (pinfunction "1_1") (pintype "passive"))
    )
    (net (code "59") (name "/PD4") (class "Default")
      (node (ref "J2") (pin "10") (pinfunction "10_10") (pintype "passive"))
    )
    (net (code "60") (name "/PD5") (class "Default")
      (node (ref "J2") (pin "11") (pinfunction "11_11") (pintype "passive"))
    )
    (net (code "61") (name "/PD6") (class "Default")
      (node (ref "J2") (pin "12") (pinfunction "12_12") (pintype "passive"))
    )
    (net (code "62") (name "/PD7") (class "Default")
      (node (ref "J2") (pin "13") (pinfunction "13_13") (pintype "passive"))
    )
    (net (code "63") (name "/PD8") (class "Default")
      (node (ref "J2") (pin "56") (pinfunction "56_56") (pintype "passive"))
      (node (ref "J4") (pin "3") (pinfunction "3_3") (pintype "passive"))
    )
    (net (code "64") (name "/PD9") (class "Default")
      (node (ref "J2") (pin "55") (pinfunction "55_55") (pintype "passive"))
      (node (ref "J7") (pin "3") (pinfunction "3_3") (pintype "passive"))
    )
    (net (code "65") (name "/PD10") (class "Default")
      (node (ref "J2") (pin "54") (pinfunction "54_54") (pintype "passive"))
      (node (ref "J5") (pin "3") (pinfunction "3_3") (pintype "passive"))
    )
    (net (code "66") (name "/PD11") (class "Default")
      (node (ref "J2") (pin "53") (pinfunction "53_53") (pintype "passive"))
      (node (ref "J6") (pin "3") (pinfunction "3_3") (pintype "passive"))
    )
    (net (code "67") (name "/PD12") (class "Default")
      (node (ref "J2") (pin "52") (pinfunction "52_52") (pintype "passive"))
      (node (ref "J3") (pin "2") (pinfunction "2_2") (pintype "passive"))
    )
    (net (code "68") (name "/PD13") (class "Default")
      (node (ref "J2") (pin "51") (pinfunction "51_51") (pintype "passive"))
      (node (ref "J4") (pin "2") (pinfunction "2_2") (pintype "passive"))
    )
    (net (code "69") (name "/PD14") (class "Default")
      (node (ref "J2") (pin "50") (pinfunction "50_50") (pintype "passive"))
      (node (ref "J7") (pin "2") (pinfunction "2_2") (pintype "passive"))
    )
    (net (code "70") (name "/PD15") (class "Default")
      (node (ref "J2") (pin "49") (pinfunction "49_49") (pintype "passive"))
      (node (ref "J5") (pin "2") (pinfunction "2_2") (pintype "passive"))
    )
    (net (code "71") (name "/PE0") (class "Default")
      (node (ref "J2") (pin "28") (pinfunction "28_28") (pintype "passive"))
    )
    (net (code "72") (name "/PE1") (class "Default")
      (node (ref "J2") (pin "29") (pinfunction "29_29") (pintype "passive"))
    )
    (net (code "73") (name "/PE2") (class "Default")
      (node (ref "C17") (pin "2") (pinfunction "2_2") (pintype "passive"))
      (node (ref "J1") (pin "30") (pinfunction "30_30") (pintype "passive"))
      (node (ref "SW2") (pin "1") (pinfunction "1_1") (pintype "passive"))
    )
    (net (code "74") (name "/PE3") (class "Default")
      (node (ref "C14") (pin "2") (pinfunction "2_2") (pintype "passive"))
      (node (ref "J1") (pin "29") (pinfunction "29_29") (pintype "passive"))
      (node (ref "SW1") (pin "1") (pinfunction "1_1") (pintype "passive"))
    )
    (net (code "75") (name "/PE4") (class "Default")
      (node (ref "J1") (pin "28") (pinfunction "28_28") (pintype "passive"))
    )
    (net (code "76") (name "/PE5") (class "Default")
      (node (ref "J1") (pin "27") (pinfunction "27_27") (pintype "passive"))
    )
    (net (code "77") (name "/PE6") (class "Default")
      (node (ref "J1") (pin "26") (pinfunction "26_26") (pintype "passive"))
    )
    (net (code "78") (name "/PE7") (class "Default")
      (node (ref "J1") (pin "50") (pinfunction "50_50") (pintype "passive"))
    )
    (net (code "79") (name "/PE8") (class "Default")
      (node (ref "J1") (pin "51") (pinfunction "51_51") (pintype "passive"))
    )
    (net (code "80") (name "/PE9") (class "Default")
      (node (ref "J1") (pin "52") (pinfunction "52_52") (pintype "passive"))
    )
    (net (code "81") (name "/PE10") (class "Default")
      (node (ref "J1") (pin "53") (pinfunction "53_53") (pintype "passive"))
    )
    (net (code "82") (name "/PE11") (class "Default")
      (node (ref "J1") (pin "54") (pinfunction "54_54") (pintype "passive"))
    )
    (net (code "83") (name "/PE12") (class "Default")
      (node (ref "J1") (pin "55") (pinfunction "55_55") (pintype "passive"))
    )
    (net (code "84") (name "/PE13") (class "Default")
      (node (ref "J1") (pin "56") (pinfunction "56_56") (pintype "passive"))
    )
    (net (code "85") (name "/PE14") (class "Default")
      (node (ref "J1") (pin "57") (pinfunction "57_57") (pintype "passive"))
    )
    (net (code "86") (name "/PE15") (class "Default")
      (node (ref "J1") (pin "58") (pinfunction "58_58") (pintype "passive"))
    )
    (net (code "87") (name "/PF0") (class "Default")
      (node (ref "J1") (pin "22") (pinfunction "22_22") (pintype "passive"))
      (node (ref "R2") (pin "1") (pinfunction "1_1") (pintype "passive"))
      (node (ref "U1") (pin "12") (pinfunction "SDA_12") (pintype "passive"))
    )
    (net (code "88") (name "/PF1") (class "Default")
      (node (ref "J1") (pin "21") (pinfunction "21_21") (pintype "passive"))
      (node (ref "R1") (pin "1") (pinfunction "1_1") (pintype "passive"))
      (node (ref "U1") (pin "11") (pinfunction "SCL_11") (pintype "passive"))
    )
    (net (code "89") (name "/PF2") (class "Default")
      (node (ref "J1") (pin "20") (pinfunction "20_20") (pintype "passive"))
      (node (ref "J16") (pin "2") (pinfunction "2_2") (pintype "passive"))
    )
    (net (code "90") (name "/PF3") (class "Default")
      (node (ref "J1") (pin "19") (pinfunction "19_19") (pintype "passive"))
      (node (ref "J17") (pin "2") (pinfunction "2_2") (pintype "passive"))
    )
    (net (code "91") (name "/PF4") (class "Default")
      (node (ref "J1") (pin "18") (pinfunction "18_18") (pintype "passive"))
      (node (ref "J18") (pin "2") (pinfunction "2_2") (pintype "passive"))
    )
    (net (code "92") (name "/PF5") (class "Default")
      (node (ref "J1") (pin "17") (pinfunction "17_17") (pintype "passive"))
      (node (ref "J19") (pin "2") (pinfunction "2_2") (pintype "passive"))
    )
    (net (code "93") (name "/PF6") (class "Default")
      (node (ref "J1") (pin "16") (pinfunction "16_16") (pintype "passive"))
    )
    (net (code "94") (name "/PF7") (class "Default")
      (node (ref "J1") (pin "15") (pinfunction "15_15") (pintype "passive"))
    )
    (net (code "95") (name "/PF8") (class "Default")
      (node (ref "J1") (pin "14") (pinfunction "14_14") (pintype "passive"))
    )
    (net (code "96") (name "/PF9") (class "Default")
      (node (ref "J1") (pin "13") (pinfunction "13_13") (pintype "passive"))
    )
    (net (code "97") (name "/PF10") (class "Default")
      (node (ref "J1") (pin "12") (pinfunction "12_12") (pintype "passive"))
    )
    (net (code "98") (name "/PF11") (class "Default")
      (node (ref "J1") (pin "43") (pinfunction "43_43") (pintype "passive"))
    )
    (net (code "99") (name "/PF12") (class "Default")
      (node (ref "J1") (pin "44") (pinfunction "44_44") (pintype "passive"))
    )
    (net (code "100") (name "/PF13") (class "Default")
      (node (ref "J1") (pin "45") (pinfunction "45_45") (pintype "passive"))
    )
    (net (code "101") (name "/PF14") (class "Default")
      (node (ref "J1") (pin "46") (pinfunction "46_46") (pintype "passive"))
    )
    (net (code "102") (name "/PF15") (class "Default")
      (node (ref "J1") (pin "47") (pinfunction "47_47") (pintype "passive"))
    )
    (net (code "103") (name "/PG0") (class "Default")
      (node (ref "J1") (pin "48") (pinfunction "48_48") (pintype "passive"))
    )
    (net (code "104") (name "/PG1") (class "Default")
      (node (ref "J1") (pin "49") (pinfunction "49_49") (pintype "passive"))
    )
    (net (code "105") (name "/PG2") (class "Default")
      (node (ref "J2") (pin "48") (pinfunction "48_48") (pintype "passive"))
    )
    (net (code "106") (name "/PG3") (class "Default")
      (node (ref "J2") (pin "47") (pinfunction "47_47") (pintype "passive"))
      (node (ref "J9") (pin "3") (pinfunction "3_3") (pintype "passive"))
    )
    (net (code "107") (name "/PG4") (class "Default")
      (node (ref "J2") (pin "46") (pinfunction "46_46") (pintype "passive"))
      (node (ref "J9") (pin "2") (pinfunction "2_2") (pintype "passive"))
    )
    (net (code "108") (name "/PG5") (class "Default")
      (node (ref "J10") (pin "3") (pinfunction "3_3") (pintype "passive"))
      (node (ref "J2") (pin "45") (pinfunction "45_45") (pintype "passive"))
    )
    (net (code "109") (name "/PG6") (class "Default")
      (node (ref "J10") (pin "2") (pinfunction "2_2") (pintype "passive"))
      (node (ref "J2") (pin "44") (pinfunction "44_44") (pintype "passive"))
    )
    (net (code "110") (name "/PG7") (class "Default")
      (node (ref "J14") (pin "3") (pinfunction "3_3") (pintype "passive"))
      (node (ref "J2") (pin "43") (pinfunction "43_43") (pintype "passive"))
    )
    (net (code "111") (name "/PG8") (class "Default")
      (node (ref "J14") (pin "2") (pinfunction "2_2") (pintype "passive"))
      (node (ref "J2") (pin "42") (pinfunction "42_42") (pintype "passive"))
    )
    (net (code "112") (name "/PG9") (class "Default")
      (node (ref "J2") (pin "14") (pinfunction "14_14") (pintype "passive"))
    )
    (net (code "113") (name "/PG10") (class "Default")
      (node (ref "J2") (pin "15") (pinfunction "15_15") (pintype "passive"))
    )
    (net (code "114") (name "/PG11") (class "Default")
      (node (ref "IC2") (pin "16") (pinfunction "TXEN_16") (pintype "passive"))
      (node (ref "J2") (pin "16") (pinfunction "16_16") (pintype "passive"))
    )
    (net (code "115") (name "/PG12") (class "Default")
      (node (ref "J2") (pin "17") (pinfunction "17_17") (pintype "passive"))
    )
    (net (code "116") (name "/PG13") (class "Default")
      (node (ref "IC2") (pin "17") (pinfunction "TXD0_17") (pintype "passive"))
      (node (ref "J2") (pin "18") (pinfunction "18_18") (pintype "passive"))
    )
    (net (code "117") (name "/PG14") (class "Default")
      (node (ref "IC2") (pin "18") (pinfunction "TXD1_18") (pintype "passive"))
      (node (ref "J2") (pin "19") (pinfunction "19_19") (pintype "passive"))
    )
    (net (code "118") (name "/PG15") (class "Default")
      (node (ref "J2") (pin "20") (pinfunction "20_20") (pintype "passive"))
    )
    (net (code "119") (name "/RS232_RX") (class "Default")
      (node (ref "IC1") (pin "8") (pinfunction "R2IN_8") (pintype "passive"))
      (node (ref "J8") (pin "3") (pinfunction "3_3") (pintype "passive"))
    )
    (net (code "120") (name "/RS232_TX") (class "Default")
      (node (ref "IC1") (pin "7") (pinfunction "T2OUT_7") (pintype "passive"))
      (node (ref "J8") (pin "2") (pinfunction "2_2") (pintype "passive"))
    )
    (net (code "121") (name "GBAT") (class "Default")
      (node (ref "C15") (pin "2") (pinfunction "2_2") (pintype "passive"))
      (node (ref "C25") (pin "2") (pinfunction "2_2") (pintype "passive"))
      (node (ref "D3") (pin "1") (pinfunction "1_1") (pintype "passive"))
      (node (ref "P1") (pin "2") (pinfunction "-_2") (pintype "passive"))
      (node (ref "P2") (pin "2") (pinfunction "-_2") (pintype "passive"))
      (node (ref "PS1") (pin "2") (pinfunction "GND_2") (pintype "passive"))
      (node (ref "PS2") (pin "2") (pinfunction "GND_2") (pintype "passive"))
    )
    (net (code "122") (name "GND") (class "Default")
      (node (ref "C1") (pin "2") (pinfunction "2_2") (pintype "passive"))
      (node (ref "C10") (pin "1") (pinfunction "1_1") (pintype "passive"))
      (node (ref "C11") (pin "2") (pinfunction "2_2") (pintype "passive"))
      (node (ref "C12") (pin "2") (pinfunction "2_2") (pintype "passive"))
      (node (ref "C13") (pin "1") (pinfunction "1_1") (pintype "passive"))
      (node (ref "C14") (pin "1") (pinfunction "1_1") (pintype "passive"))
      (node (ref "C16") (pin "2") (pinfunction "2_2") (pintype "passive"))
      (node (ref "C17") (pin "1") (pinfunction "1_1") (pintype "passive"))
      (node (ref "C18") (pin "1") (pinfunction "1_1") (pintype "passive"))
      (node (ref "C19") (pin "1") (pinfunction "1_1") (pintype "passive"))
      (node (ref "C2") (pin "2") (pinfunction "2_2") (pintype "passive"))
      (node (ref "C20") (pin "1") (pinfunction "1_1") (pintype "passive"))
      (node (ref "C21") (pin "1") (pinfunction "1_1") (pintype "passive"))
      (node (ref "C22") (pin "1") (pinfunction "1_1") (pintype "passive"))
      (node (ref "C23") (pin "1") (pinfunction "1_1") (pintype "passive"))
      (node (ref "C24") (pin "1") (pinfunction "1_1") (pintype "passive"))
      (node (ref "C26") (pin "2") (pinfunction "2_2") (pintype "passive"))
      (node (ref "C3") (pin "1") (pinfunction "1_1") (pintype "passive"))
      (node (ref "C6") (pin "1") (pinfunction "1_1") (pintype "passive"))
      (node (ref "C7") (pin "1") (pinfunction "1_1") (pintype "passive"))
      (node (ref "C8") (pin "2") (pinfunction "2_2") (pintype "passive"))
      (node (ref "C9") (pin "2") (pinfunction "2_2") (pintype "passive"))
      (node (ref "D1") (pin "1") (pinfunction "1_1") (pintype "passive"))
      (node (ref "D4") (pin "K") (pinfunction "K_K") (pintype "passive"))
      (node (ref "D5") (pin "K") (pinfunction "K_K") (pintype "passive"))
      (node (ref "D6") (pin "K") (pinfunction "K_K") (pintype "passive"))
      (node (ref "IC1") (pin "15") (pinfunction "GND_15") (pintype "passive"))
      (node (ref "IC2") (pin "25") (pinfunction "VSS_25") (pintype "passive"))
      (node (ref "J1") (pin "31") (pinfunction "31_31") (pintype "passive"))
      (node (ref "J1") (pin "32") (pinfunction "32_32") (pintype "passive"))
      (node (ref "J10") (pin "1") (pinfunction "1_1") (pintype "passive"))
      (node (ref "J12") (pin "1") (pinfunction "1_1") (pintype "passive"))
      (node (ref "J13") (pin "1") (pinfunction "1_1") (pintype "passive"))
      (node (ref "J14") (pin "1") (pinfunction "1_1") (pintype "passive"))
      (node (ref "J16") (pin "3") (pinfunction "3_3") (pintype "passive"))
      (node (ref "J17") (pin "3") (pinfunction "3_3") (pintype "passive"))
      (node (ref "J18") (pin "3") (pinfunction "3_3") (pintype "passive"))
      (node (ref "J19") (pin "3") (pinfunction "3_3") (pintype "passive"))
      (node (ref "J2") (pin "30") (pinfunction "30_30") (pintype "passive"))
      (node (ref "J2") (pin "31") (pinfunction "31_31") (pintype "passive"))
      (node (ref "J3") (pin "1") (pinfunction "1_1") (pintype "passive"))
      (node (ref "J4") (pin "1") (pinfunction "1_1") (pintype "passive"))
      (node (ref "J5") (pin "1") (pinfunction "1_1") (pintype "passive"))
      (node (ref "J6") (pin "1") (pinfunction "1_1") (pintype "passive"))
      (node (ref "J7") (pin "1") (pinfunction "1_1") (pintype "passive"))
      (node (ref "J8") (pin "5") (pinfunction "5_5") (pintype "passive"))
      (node (ref "J9") (pin "1") (pinfunction "1_1") (pintype "passive"))
      (node (ref "PS1") (pin "5") (pinfunction "0V_5") (pintype "passive"))
      (node (ref "PS2") (pin "6") (pinfunction "0V_6") (pintype "passive"))
      (node (ref "Q1") (pin "2") (pinfunction "E_2") (pintype "passive"))
      (node (ref "R20") (pin "1") (pinfunction "1_1") (pintype "passive"))
      (node (ref "R21") (pin "1") (pinfunction "1_1") (pintype "passive"))
      (node (ref "R23") (pin "2") (pinfunction "2_2") (pintype "passive"))
      (node (ref "R24") (pin "2") (pinfunction "2_2") (pintype "passive"))
      (node (ref "R4") (pin "1") (pinfunction "1_1") (pintype "passive"))
      (node (ref "R5") (pin "1") (pinfunction "1_1") (pintype "passive"))
      (node (ref "RJ1") (pin "7") (pinfunction "NC_7") (pintype "passive"))
      (node (ref "RJ1") (pin "8") (pinfunction "NC_8") (pintype "passive"))
      (node (ref "RJ1") (pin "MH1") (pinfunction "MH1_MH1") (pintype "passive"))
      (node (ref "RJ1") (pin "MH2") (pinfunction "MH2_MH2") (pintype "passive"))
      (node (ref "RJ1") (pin "MH3") (pinfunction "MH3_MH3") (pintype "passive"))
      (node (ref "RJ1") (pin "MH4") (pinfunction "MH4_MH4") (pintype "passive"))
      (node (ref "SW1") (pin "2") (pinfunction "2_2") (pintype "passive"))
      (node (ref "SW2") (pin "2") (pinfunction "2_2") (pintype "passive"))
      (node (ref "U1") (pin "8") (pinfunction "GND_8") (pintype "passive"))
      (node (ref "U2") (pin "2") (pinfunction "GND_2") (pintype "passive"))
      (node (ref "U2") (pin "8") (pinfunction "RS_8") (pintype "passive"))
      (node (ref "U3") (pin "2") (pinfunction "GND_2") (pintype "passive"))
      (node (ref "U3") (pin "8") (pinfunction "RS_8") (pintype "passive"))
      (node (ref "X1") (pin "2") (pinfunction "GND_2") (pintype "passive"))
    )
    (net (code "123") (name "Net-(BUZZER1--)") (class "Default")
      (node (ref "BUZZER1") (pin "2") (pinfunction "-_2") (pintype "passive"))
      (node (ref "Q1") (pin "3") (pinfunction "C_3") (pintype "passive"))
    )
    (net (code "124") (name "Net-(C8-Pad1)") (class "Default")
      (node (ref "C8") (pin "1") (pinfunction "1_1") (pintype "passive"))
      (node (ref "R6") (pin "2") (pinfunction "2_2") (pintype "passive"))
      (node (ref "R8") (pin "1") (pinfunction "1_1") (pintype "passive"))
    )
    (net (code "125") (name "Net-(C9-Pad1)") (class "Default")
      (node (ref "C9") (pin "1") (pinfunction "1_1") (pintype "passive"))
      (node (ref "R7") (pin "1") (pinfunction "1_1") (pintype "passive"))
      (node (ref "R9") (pin "2") (pinfunction "2_2") (pintype "passive"))
    )
    (net (code "126") (name "Net-(C11-Pad1)") (class "Default")
      (node (ref "C11") (pin "1") (pinfunction "1_1") (pintype "passive"))
      (node (ref "R10") (pin "2") (pinfunction "2_2") (pintype "passive"))
      (node (ref "R12") (pin "1") (pinfunction "1_1") (pintype "passive"))
    )
    (net (code "127") (name "Net-(C12-Pad1)") (class "Default")
      (node (ref "C12") (pin "1") (pinfunction "1_1") (pintype "passive"))
      (node (ref "R11") (pin "1") (pinfunction "1_1") (pintype "passive"))
      (node (ref "R13") (pin "2") (pinfunction "2_2") (pintype "passive"))
    )
    (net (code "128") (name "Net-(D1-Pad2)") (class "Default")
      (node (ref "D1") (pin "2") (pinfunction "2_2") (pintype "passive"))
      (node (ref "J8") (pin "MH1") (pinfunction "MH1_MH1") (pintype "passive"))
      (node (ref "J8") (pin "MH2") (pinfunction "MH2_MH2") (pintype "passive"))
      (node (ref "R4") (pin "2") (pinfunction "2_2") (pintype "passive"))
    )
    (net (code "129") (name "Net-(D2-A)") (class "Default")
      (node (ref "D2") (pin "1") (pinfunction "A_1") (pintype "passive"))
      (node (ref "D3") (pin "2") (pinfunction "2_2") (pintype "passive"))
      (node (ref "F1") (pin "2") (pinfunction "2_2") (pintype "passive"))
    )
    (net (code "130") (name "Net-(D4-PadA)") (class "Default")
      (node (ref "D4") (pin "A") (pinfunction "A_A") (pintype "passive"))
      (node (ref "R19") (pin "1") (pinfunction "1_1") (pintype "passive"))
    )
    (net (code "131") (name "Net-(D5-PadA)") (class "Default")
      (node (ref "D5") (pin "A") (pinfunction "A_A") (pintype "passive"))
      (node (ref "R22") (pin "1") (pinfunction "1_1") (pintype "passive"))
    )
    (net (code "132") (name "Net-(D6-PadA)") (class "Default")
      (node (ref "D6") (pin "A") (pinfunction "A_A") (pintype "passive"))
      (node (ref "R25") (pin "1") (pinfunction "1_1") (pintype "passive"))
    )
    (net (code "133") (name "Net-(IC1-C1+)") (class "Default")
      (node (ref "C4") (pin "2") (pinfunction "2_2") (pintype "passive"))
      (node (ref "IC1") (pin "1") (pinfunction "C1+_1") (pintype "passive"))
    )
    (net (code "134") (name "Net-(IC1-C1-)") (class "Default")
      (node (ref "C4") (pin "1") (pinfunction "1_1") (pintype "passive"))
      (node (ref "IC1") (pin "3") (pinfunction "C1-_3") (pintype "passive"))
    )
    (net (code "135") (name "Net-(IC1-C2+)") (class "Default")
      (node (ref "C5") (pin "2") (pinfunction "2_2") (pintype "passive"))
      (node (ref "IC1") (pin "4") (pinfunction "C2+_4") (pintype "passive"))
    )
    (net (code "136") (name "Net-(IC1-C2-)") (class "Default")
      (node (ref "C5") (pin "1") (pinfunction "1_1") (pintype "passive"))
      (node (ref "IC1") (pin "5") (pinfunction "C2-_5") (pintype "passive"))
    )
    (net (code "137") (name "Net-(IC1-V+)") (class "Default")
      (node (ref "C6") (pin "2") (pinfunction "2_2") (pintype "passive"))
      (node (ref "IC1") (pin "2") (pinfunction "V+_2") (pintype "passive"))
    )
    (net (code "138") (name "Net-(IC1-V-)") (class "Default")
      (node (ref "C7") (pin "2") (pinfunction "2_2") (pintype "passive"))
      (node (ref "IC1") (pin "6") (pinfunction "V-_6") (pintype "passive"))
    )
    (net (code "139") (name "Net-(IC2-MDIO)") (class "Default")
      (node (ref "IC2") (pin "12") (pinfunction "MDIO_12") (pintype "passive"))
      (node (ref "R18") (pin "1") (pinfunction "1_1") (pintype "passive"))
    )
    (net (code "140") (name "Net-(IC2-RBIAS)") (class "Default")
      (node (ref "IC2") (pin "24") (pinfunction "RBIAS_24") (pintype "passive"))
      (node (ref "R24") (pin "1") (pinfunction "1_1") (pintype "passive"))
    )
    (net (code "141") (name "Net-(IC2-RXN)") (class "Default")
      (node (ref "C23") (pin "2") (pinfunction "2_2") (pintype "passive"))
      (node (ref "IC2") (pin "22") (pinfunction "RXN_22") (pintype "passive"))
      (node (ref "R17") (pin "1") (pinfunction "1_1") (pintype "passive"))
      (node (ref "RJ1") (pin "6") (pinfunction "RD-_6") (pintype "passive"))
    )
    (net (code "142") (name "Net-(IC2-RXP)") (class "Default")
      (node (ref "C22") (pin "2") (pinfunction "2_2") (pintype "passive"))
      (node (ref "IC2") (pin "23") (pinfunction "RXP_23") (pintype "passive"))
      (node (ref "R16") (pin "1") (pinfunction "1_1") (pintype "passive"))
      (node (ref "RJ1") (pin "3") (pinfunction "RD+_3") (pintype "passive"))
    )
    (net (code "143") (name "Net-(IC2-TXN)") (class "Default")
      (node (ref "C21") (pin "2") (pinfunction "2_2") (pintype "passive"))
      (node (ref "IC2") (pin "20") (pinfunction "TXN_20") (pintype "passive"))
      (node (ref "R15") (pin "1") (pinfunction "1_1") (pintype "passive"))
      (node (ref "RJ1") (pin "2") (pinfunction "TD-_2") (pintype "passive"))
    )
    (net (code "144") (name "Net-(IC2-TXP)") (class "Default")
      (node (ref "C20") (pin "2") (pinfunction "2_2") (pintype "passive"))
      (node (ref "IC2") (pin "21") (pinfunction "TXP_21") (pintype "passive"))
      (node (ref "R14") (pin "1") (pinfunction "1_1") (pintype "passive"))
      (node (ref "RJ1") (pin "1") (pinfunction "TD+_1") (pintype "passive"))
    )
    (net (code "145") (name "Net-(IC2-XTAL1{slash}CLKIN)") (class "Default")
      (node (ref "IC2") (pin "5") (pinfunction "XTAL1/CLKIN_5") (pintype "passive"))
      (node (ref "X1") (pin "3") (pinfunction "OSC2_3") (pintype "passive"))
    )
    (net (code "146") (name "Net-(IC2-XTAL2)") (class "Default")
      (node (ref "IC2") (pin "4") (pinfunction "XTAL2_4") (pintype "passive"))
      (node (ref "X1") (pin "1") (pinfunction "OSC1_1") (pintype "passive"))
    )
    (net (code "147") (name "Net-(P1-+)") (class "Default")
      (node (ref "F1") (pin "1") (pinfunction "1_1") (pintype "passive"))
      (node (ref "P1") (pin "1") (pinfunction "+_1") (pintype "passive"))
      (node (ref "P2") (pin "1") (pinfunction "+_1") (pintype "passive"))
    )
    (net (code "148") (name "Net-(Q1-B)") (class "Default")
      (node (ref "Q1") (pin "1") (pinfunction "B_1") (pintype "passive"))
      (node (ref "R3") (pin "2") (pinfunction "2_2") (pintype "passive"))
      (node (ref "R5") (pin "2") (pinfunction "2_2") (pintype "passive"))
    )
    (net (code "149") (name "Net-(RJ1-LED(Y)_A)") (class "Default")
      (node (ref "R20") (pin "2") (pinfunction "2_2") (pintype "passive"))
      (node (ref "RJ1") (pin "12") (pinfunction "LED(Y)_A_12") (pintype "passive"))
    )
    (net (code "150") (name "Net-(RJ1-LED(Y)_K)") (class "Default")
      (node (ref "R21") (pin "2") (pinfunction "2_2") (pintype "passive"))
      (node (ref "RJ1") (pin "11") (pinfunction "LED(Y)_K_11") (pintype "passive"))
    )
    (net (code "151") (name "VBAT") (class "Default")
      (node (ref "C15") (pin "1") (pinfunction "1_1") (pintype "passive"))
      (node (ref "C25") (pin "1") (pinfunction "1_1") (pintype "passive"))
      (node (ref "D2") (pin "2") (pinfunction "K_2") (pintype "passive"))
      (node (ref "PS1") (pin "3") (pinfunction "VIN_3") (pintype "passive"))
      (node (ref "PS2") (pin "3") (pinfunction "VIN_3") (pintype "passive"))
    )
    (net (code "152") (name "VCC_3V3") (class "Default")
      (node (ref "C18") (pin "2") (pinfunction "2_2") (pintype "passive"))
      (node (ref "IC2") (pin "9") (pinfunction "VDDIO_9") (pintype "passive"))
      (node (ref "J1") (pin "3") (pinfunction "3_3") (pintype "passive"))
      (node (ref "J1") (pin "4") (pinfunction "4_4") (pintype "passive"))
      (node (ref "L1") (pin "1") (pinfunction "1_1") (pintype "passive"))
    )
    (net (code "153") (name "VCC_3V3E") (class "Default")
      (node (ref "C19") (pin "2") (pinfunction "2_2") (pintype "passive"))
      (node (ref "C24") (pin "2") (pinfunction "2_2") (pintype "passive"))
      (node (ref "IC2") (pin "1") (pinfunction "VDD2A_1") (pintype "passive"))
      (node (ref "IC2") (pin "19") (pinfunction "VDD1A_19") (pintype "passive"))
      (node (ref "L1") (pin "2") (pinfunction "2_2") (pintype "passive"))
      (node (ref "R14") (pin "2") (pinfunction "2_2") (pintype "passive"))
      (node (ref "R15") (pin "2") (pinfunction "2_2") (pintype "passive"))
      (node (ref "R16") (pin "2") (pinfunction "2_2") (pintype "passive"))
      (node (ref "R17") (pin "2") (pinfunction "2_2") (pintype "passive"))
      (node (ref "RJ1") (pin "4") (pinfunction "TCT_4") (pintype "passive"))
      (node (ref "RJ1") (pin "5") (pinfunction "RCT_5") (pintype "passive"))
    )
    (net (code "154") (name "VCC_5V") (class "Default")
      (node (ref "C1") (pin "1") (pinfunction "1_1") (pintype "passive"))
      (node (ref "C10") (pin "2") (pinfunction "2_2") (pintype "passive"))
      (node (ref "C13") (pin "2") (pinfunction "2_2") (pintype "passive"))
      (node (ref "C2") (pin "1") (pinfunction "1_1") (pintype "passive"))
      (node (ref "C26") (pin "1") (pinfunction "1_1") (pintype "passive"))
      (node (ref "C3") (pin "2") (pinfunction "2_2") (pintype "passive"))
      (node (ref "IC1") (pin "16") (pinfunction "VCC_16") (pintype "passive"))
      (node (ref "J1") (pin "1") (pinfunction "1_1") (pintype "passive"))
      (node (ref "J1") (pin "2") (pinfunction "2_2") (pintype "passive"))
      (node (ref "J10") (pin "4") (pinfunction "4_4") (pintype "passive"))
      (node (ref "J14") (pin "4") (pinfunction "4_4") (pintype "passive"))
      (node (ref "J3") (pin "4") (pinfunction "4_4") (pintype "passive"))
      (node (ref "J4") (pin "4") (pinfunction "4_4") (pintype "passive"))
      (node (ref "J5") (pin "4") (pinfunction "4_4") (pintype "passive"))
      (node (ref "J6") (pin "4") (pinfunction "4_4") (pintype "passive"))
      (node (ref "J7") (pin "4") (pinfunction "4_4") (pintype "passive"))
      (node (ref "J9") (pin "4") (pinfunction "4_4") (pintype "passive"))
      (node (ref "PS2") (pin "1") (pinfunction "CTRL_1") (pintype "passive"))
      (node (ref "PS2") (pin "4") (pinfunction "+VO_4") (pintype "passive"))
      (node (ref "R1") (pin "2") (pinfunction "2_2") (pintype "passive"))
      (node (ref "R2") (pin "2") (pinfunction "2_2") (pintype "passive"))
      (node (ref "U1") (pin "1") (pinfunction "VCC_1") (pintype "passive"))
      (node (ref "U2") (pin "3") (pinfunction "VCC_3") (pintype "passive"))
      (node (ref "U3") (pin "3") (pinfunction "VCC_3") (pintype "passive"))
    )
    (net (code "155") (name "VCC_12V") (class "Default")
      (node (ref "BUZZER1") (pin "1") (pinfunction "+_1") (pintype "passive"))
      (node (ref "C16") (pin "1") (pinfunction "1_1") (pintype "passive"))
      (node (ref "J12") (pin "2") (pinfunction "2_2") (pintype "passive"))
      (node (ref "J13") (pin "2") (pinfunction "2_2") (pintype "passive"))
      (node (ref "J16") (pin "1") (pinfunction "1_1") (pintype "passive"))
      (node (ref "J17") (pin "1") (pinfunction "1_1") (pintype "passive"))
      (node (ref "J18") (pin "1") (pinfunction "1_1") (pintype "passive"))
      (node (ref "J19") (pin "1") (pinfunction "1_1") (pintype "passive"))
      (node (ref "PS1") (pin "1") (pinfunction "CTRL_1") (pintype "passive"))
      (node (ref "PS1") (pin "4") (pinfunction "+VO_4") (pintype "passive"))
    )
    (net (code "156") (name "unconnected-(IC1-R1IN-Pad13)") (class "Default")
      (node (ref "IC1") (pin "13") (pinfunction "R1IN_13") (pintype "passive+no_connect"))
    )
    (net (code "157") (name "unconnected-(IC1-R1OUT-Pad12)") (class "Default")
      (node (ref "IC1") (pin "12") (pinfunction "R1OUT_12") (pintype "passive+no_connect"))
    )
    (net (code "158") (name "unconnected-(IC1-T1IN-Pad11)") (class "Default")
      (node (ref "IC1") (pin "11") (pinfunction "T1IN_11") (pintype "passive+no_connect"))
    )
    (net (code "159") (name "unconnected-(IC1-T1OUT-Pad14)") (class "Default")
      (node (ref "IC1") (pin "14") (pinfunction "T1OUT_14") (pintype "passive+no_connect"))
    )
    (net (code "160") (name "unconnected-(IC2-RXER{slash}~{PHYAD0}-Pad10)") (class "Default")
      (node (ref "IC2") (pin "10") (pinfunction "RXER/~{PHYAD0}_10") (pintype "passive+no_connect"))
    )
    (net (code "161") (name "unconnected-(IC2-VDDCR-Pad6)") (class "Default")
      (node (ref "IC2") (pin "6") (pinfunction "VDDCR_6") (pintype "passive+no_connect"))
    )
    (net (code "162") (name "unconnected-(J8-Pad1)") (class "Default")
      (node (ref "J8") (pin "1") (pinfunction "1_1") (pintype "passive+no_connect"))
    )
    (net (code "163") (name "unconnected-(J8-Pad4)") (class "Default")
      (node (ref "J8") (pin "4") (pinfunction "4_4") (pintype "passive+no_connect"))
    )
    (net (code "164") (name "unconnected-(J8-Pad6)") (class "Default")
      (node (ref "J8") (pin "6") (pinfunction "6_6") (pintype "passive+no_connect"))
    )
    (net (code "165") (name "unconnected-(J8-Pad7)") (class "Default")
      (node (ref "J8") (pin "7") (pinfunction "7_7") (pintype "passive+no_connect"))
    )
    (net (code "166") (name "unconnected-(J8-Pad8)") (class "Default")
      (node (ref "J8") (pin "8") (pinfunction "8_8") (pintype "passive+no_connect"))
    )
    (net (code "167") (name "unconnected-(J8-Pad9)") (class "Default")
      (node (ref "J8") (pin "9") (pinfunction "9_9") (pintype "passive+no_connect"))
    )
    (net (code "168") (name "unconnected-(PS1-TRIM-Pad6)") (class "Default")
      (node (ref "PS1") (pin "6") (pinfunction "TRIM_6") (pintype "passive+no_connect"))
    )
    (net (code "169") (name "unconnected-(PS2-TRIM-Pad5)") (class "Default")
      (node (ref "PS2") (pin "5") (pinfunction "TRIM_5") (pintype "passive+no_connect"))
    )
    (net (code "170") (name "unconnected-(U1-D0-Pad2)") (class "Default")
      (node (ref "U1") (pin "2") (pinfunction "D0_2") (pintype "passive+no_connect"))
    )
    (net (code "171") (name "unconnected-(U1-D1-Pad3)") (class "Default")
      (node (ref "U1") (pin "3") (pinfunction "D1_3") (pintype "passive+no_connect"))
    )
    (net (code "172") (name "unconnected-(U1-D2-Pad4)") (class "Default")
      (node (ref "U1") (pin "4") (pinfunction "D2_4") (pintype "passive+no_connect"))
    )
    (net (code "173") (name "unconnected-(U1-D3-Pad5)") (class "Default")
      (node (ref "U1") (pin "5") (pinfunction "D3_5") (pintype "passive+no_connect"))
    )
    (net (code "174") (name "unconnected-(U1-D4-Pad6)") (class "Default")
      (node (ref "U1") (pin "6") (pinfunction "D4_6") (pintype "passive+no_connect"))
    )
    (net (code "175") (name "unconnected-(U1-D5-Pad7)") (class "Default")
      (node (ref "U1") (pin "7") (pinfunction "D5_7") (pintype "passive+no_connect"))
    )
    (net (code "176") (name "unconnected-(U1-RX-Pad13)") (class "Default")
      (node (ref "U1") (pin "13") (pinfunction "RX_13") (pintype "passive+no_connect"))
    )
    (net (code "177") (name "unconnected-(U1-SWCLK-Pad9)") (class "Default")
      (node (ref "U1") (pin "9") (pinfunction "SWCLK_9") (pintype "passive+no_connect"))
    )
    (net (code "178") (name "unconnected-(U1-SWDIO-Pad10)") (class "Default")
      (node (ref "U1") (pin "10") (pinfunction "SWDIO_10") (pintype "passive+no_connect"))
    )
    (net (code "179") (name "unconnected-(U1-TX-Pad14)") (class "Default")
      (node (ref "U1") (pin "14") (pinfunction "TX_14") (pintype "passive+no_connect"))
    )
    (net (code "180") (name "unconnected-(U2-Vref-Pad5)") (class "Default")
      (node (ref "U2") (pin "5") (pinfunction "Vref_5") (pintype "passive+no_connect"))
    )
    (net (code "181") (name "unconnected-(U3-Vref-Pad5)") (class "Default")
      (node (ref "U3") (pin "5") (pinfunction "Vref_5") (pintype "passive+no_connect"))
    )
  )
)
